# esp32_wroom_32_pwm.net
KiCad netlist of a schematic drawn in EAGLE
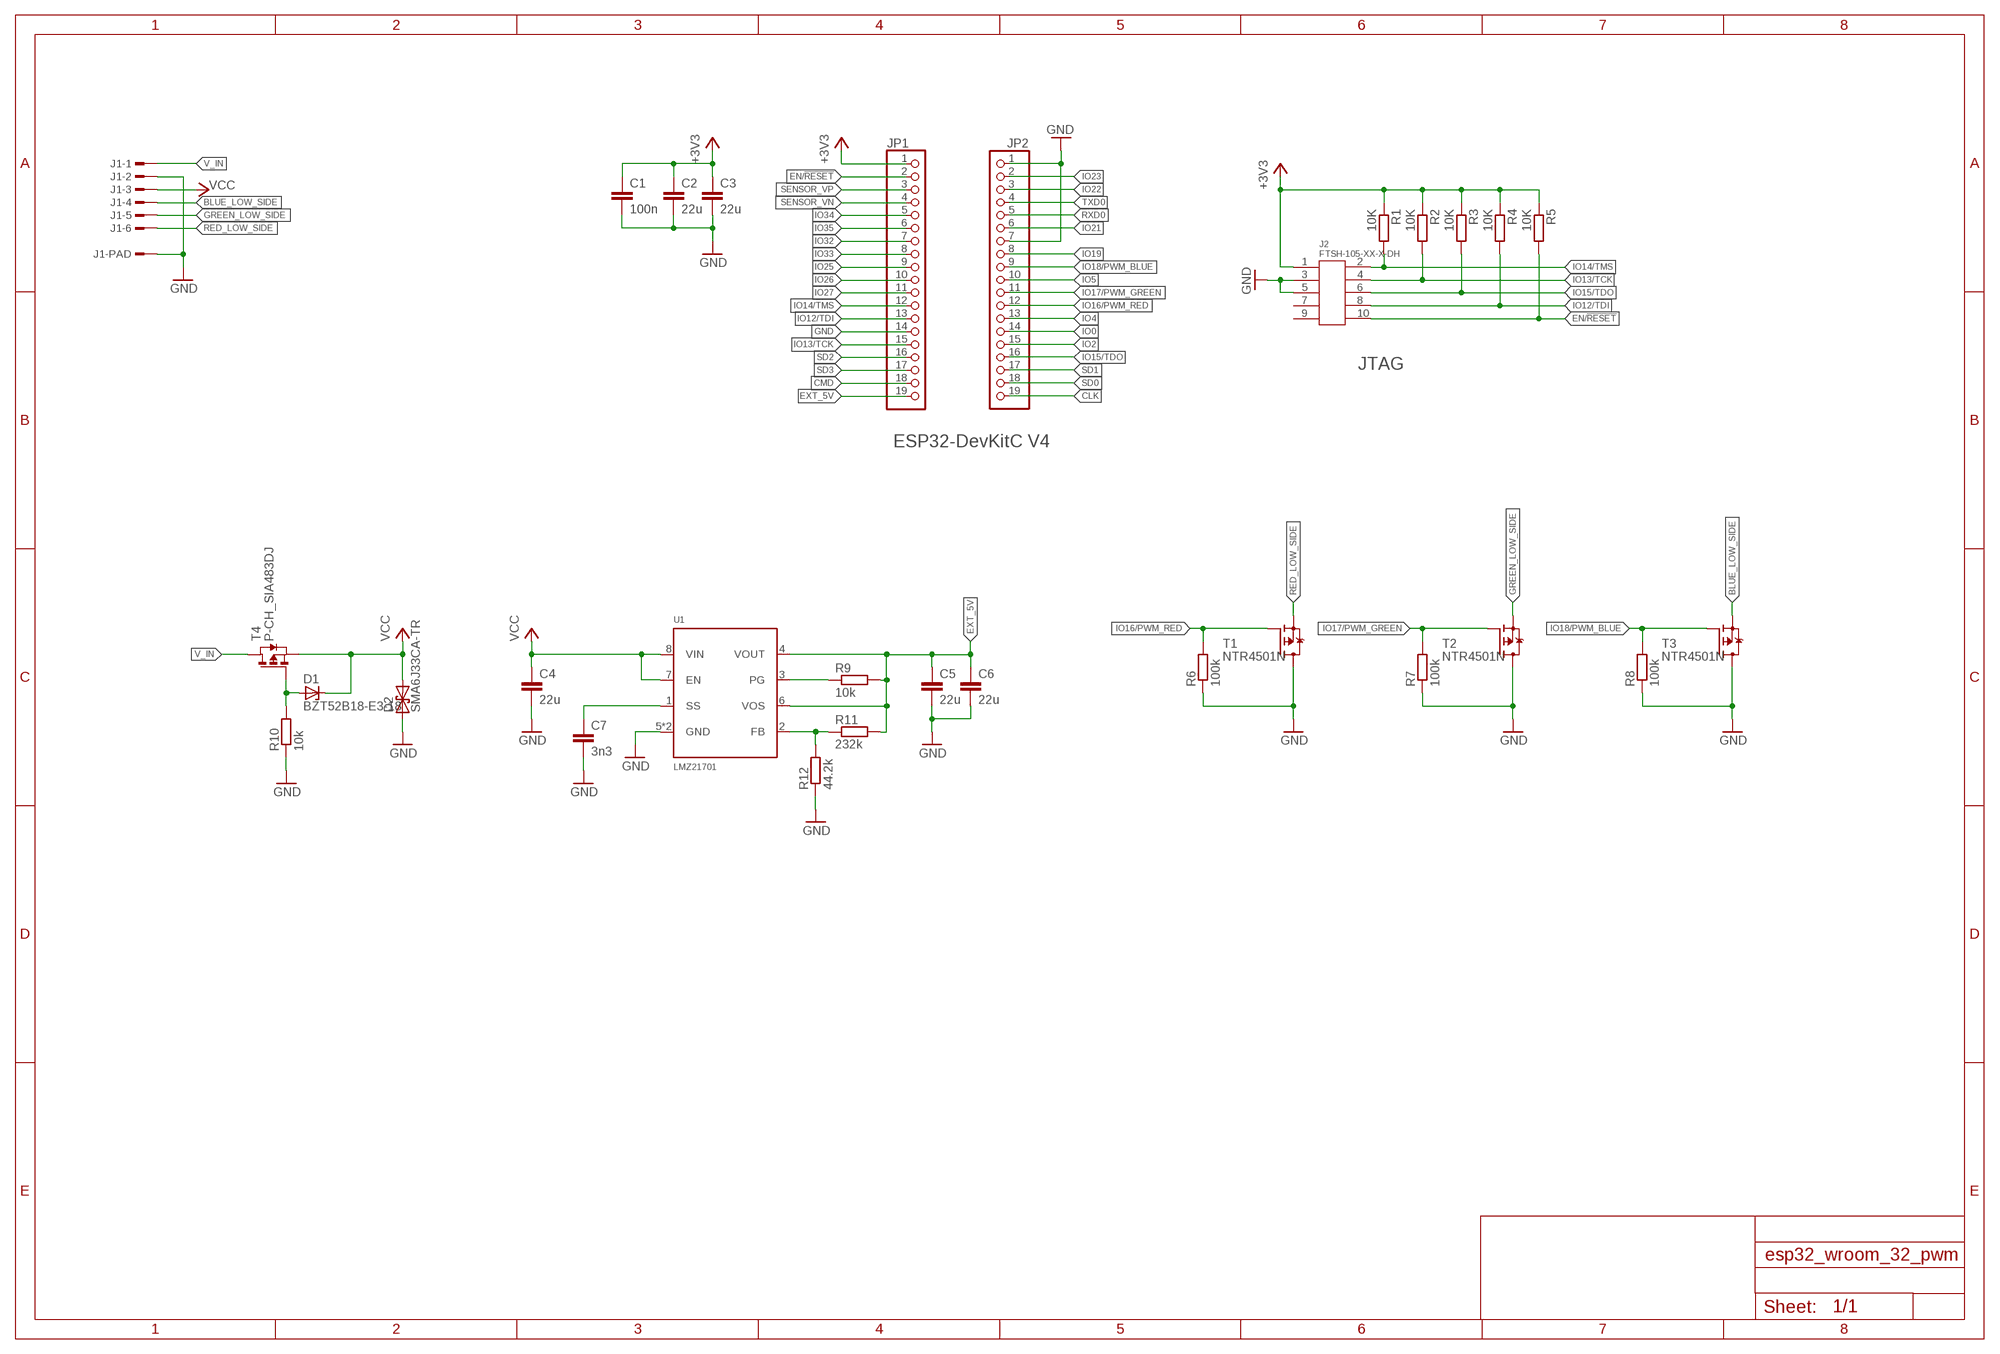
[diagram p0: schematic, sheet 1]

(export (version "E")
  (design (tool "Eeschema 10.0.6"))
  (components
    (comp (ref "C1")
      (value "100n")
      (footprint "eagle-import:C0603")
      (libsource (lib "eagle-import") (part "C-EUC0603"))
    )
    (comp (ref "C2")
      (value "22u")
      (footprint "eagle-import:C1210")
      (libsource (lib "eagle-import") (part "C-EUC1210"))
    )
    (comp (ref "C3")
      (value "22u")
      (footprint "eagle-import:C1210")
      (libsource (lib "eagle-import") (part "C-EUC1210"))
    )
    (comp (ref "C4")
      (value "22u")
      (footprint "eagle-import:C1210")
      (libsource (lib "eagle-import") (part "C-EUC1210"))
    )
    (comp (ref "C5")
      (value "22u")
      (footprint "eagle-import:C1210")
      (libsource (lib "eagle-import") (part "C-EUC1210"))
    )
    (comp (ref "C6")
      (value "22u")
      (footprint "eagle-import:C1210")
      (libsource (lib "eagle-import") (part "C-EUC1210"))
    )
    (comp (ref "C7")
      (value "3n3")
      (footprint "eagle-import:C0603")
      (libsource (lib "eagle-import") (part "C-EUC0603"))
    )
    (comp (ref "D1")
      (value "BZT52B18-E3-18")
      (footprint "eagle-import:SOD123F")
      (libsource (lib "eagle-import") (part "ZENER_BZT52B18-E3-18"))
    )
    (comp (ref "D2")
      (value "SMA6J33CA-TR")
      (footprint "eagle-import:DO214AC")
      (libsource (lib "eagle-import") (part "SMA6J33CA-TR"))
    )
    (comp (ref "J1")
      (value "292227-6")
      (footprint "eagle-import:292227-6")
      (libsource (lib "eagle-import") (part "292227-6"))
    )
    (comp (ref "J2")
      (value "FTSH-105-XX-X-DH")
      (footprint "eagle-import:FTSH-105-XX-XXX-DH")
      (libsource (lib "eagle-import") (part "FTSH-105-XX-X-DH"))
    )
    (comp (ref "JP1")
      (value "PINHD-1X19")
      (footprint "eagle-import:1X19")
      (libsource (lib "eagle-import") (part "PINHD-1X19"))
    )
    (comp (ref "JP2")
      (value "PINHD-1X19")
      (footprint "eagle-import:1X19")
      (libsource (lib "eagle-import") (part "PINHD-1X19"))
    )
    (comp (ref "R1")
      (value "10K")
      (footprint "eagle-import:R0603")
      (libsource (lib "eagle-import") (part "R-EU_R0603"))
    )
    (comp (ref "R2")
      (value "10K")
      (footprint "eagle-import:R0603")
      (libsource (lib "eagle-import") (part "R-EU_R0603"))
    )
    (comp (ref "R3")
      (value "10K")
      (footprint "eagle-import:R0603")
      (libsource (lib "eagle-import") (part "R-EU_R0603"))
    )
    (comp (ref "R4")
      (value "10K")
      (footprint "eagle-import:R0603")
      (libsource (lib "eagle-import") (part "R-EU_R0603"))
    )
    (comp (ref "R5")
      (value "10K")
      (footprint "eagle-import:R0603")
      (libsource (lib "eagle-import") (part "R-EU_R0603"))
    )
    (comp (ref "R6")
      (value "100k")
      (footprint "eagle-import:R0603")
      (libsource (lib "eagle-import") (part "R-EU_R0603"))
    )
    (comp (ref "R7")
      (value "100k")
      (footprint "eagle-import:R0603")
      (libsource (lib "eagle-import") (part "R-EU_R0603"))
    )
    (comp (ref "R8")
      (value "100k")
      (footprint "eagle-import:R0603")
      (libsource (lib "eagle-import") (part "R-EU_R0603"))
    )
    (comp (ref "R9")
      (value "10k")
      (footprint "eagle-import:R0603")
      (libsource (lib "eagle-import") (part "R-EU_R0603"))
    )
    (comp (ref "R10")
      (value "10k")
      (footprint "eagle-import:R0603")
      (libsource (lib "eagle-import") (part "R-EU_R0603"))
    )
    (comp (ref "R11")
      (value "232k")
      (footprint "eagle-import:R0603")
      (libsource (lib "eagle-import") (part "R-EU_R0603"))
    )
    (comp (ref "R12")
      (value "44.2k")
      (footprint "eagle-import:R0603")
      (libsource (lib "eagle-import") (part "R-EU_R0603"))
    )
    (comp (ref "T1")
      (value "NTR4501N")
      (footprint "eagle-import:SOT23")
      (libsource (lib "eagle-import") (part "NTR4501N"))
    )
    (comp (ref "T2")
      (value "NTR4501N")
      (footprint "eagle-import:SOT23")
      (libsource (lib "eagle-import") (part "NTR4501N"))
    )
    (comp (ref "T3")
      (value "NTR4501N")
      (footprint "eagle-import:SOT23")
      (libsource (lib "eagle-import") (part "NTR4501N"))
    )
    (comp (ref "T4")
      (value "P-CH_SIA483DJ")
      (footprint "eagle-import:POWERPAK_SC70-6L")
      (libsource (lib "eagle-import") (part "P-CH_SIA483DJ"))
    )
    (comp (ref "U1")
      (value "LMZ21701")
      (footprint "eagle-import:SIL0008E")
      (libsource (lib "eagle-import") (part "LMZ21701"))
    )
  )
  (nets
    (net (code "1") (name "+3V3") (class "Default")
      (node (ref "C1") (pin "1") (pinfunction "1_1") (pintype "passive"))
      (node (ref "C2") (pin "1") (pinfunction "1_1") (pintype "passive"))
      (node (ref "C3") (pin "1") (pinfunction "1_1") (pintype "passive"))
      (node (ref "J2") (pin "1") (pinfunction "1_1") (pintype "passive"))
      (node (ref "JP1") (pin "1") (pinfunction "1_1") (pintype "passive"))
      (node (ref "R1") (pin "1") (pinfunction "1_1") (pintype "passive"))
      (node (ref "R2") (pin "1") (pinfunction "1_1") (pintype "passive"))
      (node (ref "R3") (pin "1") (pinfunction "1_1") (pintype "passive"))
      (node (ref "R4") (pin "1") (pinfunction "1_1") (pintype "passive"))
      (node (ref "R5") (pin "1") (pinfunction "1_1") (pintype "passive"))
    )
    (net (code "2") (name "/EN{slash}~{RESET}") (class "Default")
      (node (ref "J2") (pin "10") (pinfunction "10_10") (pintype "passive"))
      (node (ref "JP1") (pin "2") (pinfunction "2_2") (pintype "passive"))
      (node (ref "R5") (pin "2") (pinfunction "2_2") (pintype "passive"))
    )
    (net (code "3") (name "BLUE_LOW_SIDE") (class "Default")
      (node (ref "J1") (pin "4") (pinfunction "1_4") (pintype "passive"))
      (node (ref "T3") (pin "2") (pinfunction "S_2") (pintype "passive"))
    )
    (net (code "4") (name "CLK") (class "Default")
      (node (ref "JP2") (pin "19") (pinfunction "19_19") (pintype "passive"))
    )
    (net (code "5") (name "CMD") (class "Default")
      (node (ref "JP1") (pin "18") (pinfunction "18_18") (pintype "passive"))
    )
    (net (code "6") (name "EXT_5V") (class "Default")
      (node (ref "C5") (pin "1") (pinfunction "1_1") (pintype "passive"))
      (node (ref "C6") (pin "1") (pinfunction "1_1") (pintype "passive"))
      (node (ref "JP1") (pin "19") (pinfunction "19_19") (pintype "passive"))
      (node (ref "R11") (pin "2") (pinfunction "2_2") (pintype "passive"))
      (node (ref "R9") (pin "2") (pinfunction "2_2") (pintype "passive"))
      (node (ref "U1") (pin "4") (pinfunction "VOUT_4") (pintype "passive"))
      (node (ref "U1") (pin "6") (pinfunction "VOS_6") (pintype "input"))
    )
    (net (code "7") (name "GND") (class "Default")
      (node (ref "C1") (pin "2") (pinfunction "2_2") (pintype "passive"))
      (node (ref "C2") (pin "2") (pinfunction "2_2") (pintype "passive"))
      (node (ref "C3") (pin "2") (pinfunction "2_2") (pintype "passive"))
      (node (ref "C4") (pin "2") (pinfunction "2_2") (pintype "passive"))
      (node (ref "C5") (pin "2") (pinfunction "2_2") (pintype "passive"))
      (node (ref "C6") (pin "2") (pinfunction "2_2") (pintype "passive"))
      (node (ref "C7") (pin "2") (pinfunction "2_2") (pintype "passive"))
      (node (ref "D2") (pin "A") (pinfunction "1_A") (pintype "passive"))
      (node (ref "J1") (pin "2") (pinfunction "1_2") (pintype "passive"))
      (node (ref "J1") (pin "PAD1") (pinfunction "1_PAD1") (pintype "passive"))
      (node (ref "J1") (pin "PAD2") (pinfunction "1_PAD2") (pintype "passive"))
      (node (ref "J2") (pin "3") (pinfunction "3_3") (pintype "passive"))
      (node (ref "J2") (pin "5") (pinfunction "5_5") (pintype "passive"))
      (node (ref "JP1") (pin "14") (pinfunction "14_14") (pintype "passive"))
      (node (ref "JP2") (pin "1") (pinfunction "1_1") (pintype "passive"))
      (node (ref "JP2") (pin "7") (pinfunction "7_7") (pintype "passive"))
      (node (ref "R10") (pin "1") (pinfunction "1_1") (pintype "passive"))
      (node (ref "R12") (pin "1") (pinfunction "1_1") (pintype "passive"))
      (node (ref "R6") (pin "1") (pinfunction "1_1") (pintype "passive"))
      (node (ref "R7") (pin "1") (pinfunction "1_1") (pintype "passive"))
      (node (ref "R8") (pin "1") (pinfunction "1_1") (pintype "passive"))
      (node (ref "T1") (pin "3") (pinfunction "D_3") (pintype "passive"))
      (node (ref "T2") (pin "3") (pinfunction "D_3") (pintype "passive"))
      (node (ref "T3") (pin "3") (pinfunction "D_3") (pintype "passive"))
      (node (ref "U1") (pin "5") (pinfunction "GND_5") (pintype "power_in"))
      (node (ref "U1") (pin "PAD") (pinfunction "GND_PAD") (pintype "power_in"))
    )
    (net (code "8") (name "GREEN_LOW_SIDE") (class "Default")
      (node (ref "J1") (pin "5") (pinfunction "1_5") (pintype "passive"))
      (node (ref "T2") (pin "2") (pinfunction "S_2") (pintype "passive"))
    )
    (net (code "9") (name "IO0") (class "Default")
      (node (ref "JP2") (pin "14") (pinfunction "14_14") (pintype "passive"))
    )
    (net (code "10") (name "IO2") (class "Default")
      (node (ref "JP2") (pin "15") (pinfunction "15_15") (pintype "passive"))
    )
    (net (code "11") (name "IO4") (class "Default")
      (node (ref "JP2") (pin "13") (pinfunction "13_13") (pintype "passive"))
    )
    (net (code "12") (name "IO5") (class "Default")
      (node (ref "JP2") (pin "10") (pinfunction "10_10") (pintype "passive"))
    )
    (net (code "13") (name "IO12{slash}TDI") (class "Default")
      (node (ref "J2") (pin "8") (pinfunction "8_8") (pintype "passive"))
      (node (ref "JP1") (pin "13") (pinfunction "13_13") (pintype "passive"))
      (node (ref "R4") (pin "2") (pinfunction "2_2") (pintype "passive"))
    )
    (net (code "14") (name "IO13{slash}TCK") (class "Default")
      (node (ref "J2") (pin "4") (pinfunction "4_4") (pintype "passive"))
      (node (ref "JP1") (pin "15") (pinfunction "15_15") (pintype "passive"))
      (node (ref "R2") (pin "2") (pinfunction "2_2") (pintype "passive"))
    )
    (net (code "15") (name "IO14{slash}TMS") (class "Default")
      (node (ref "J2") (pin "2") (pinfunction "2_2") (pintype "passive"))
      (node (ref "JP1") (pin "12") (pinfunction "12_12") (pintype "passive"))
      (node (ref "R1") (pin "2") (pinfunction "2_2") (pintype "passive"))
    )
    (net (code "16") (name "IO15{slash}TDO") (class "Default")
      (node (ref "J2") (pin "6") (pinfunction "6_6") (pintype "passive"))
      (node (ref "JP2") (pin "16") (pinfunction "16_16") (pintype "passive"))
      (node (ref "R3") (pin "2") (pinfunction "2_2") (pintype "passive"))
    )
    (net (code "17") (name "IO16{slash}PWM_RED") (class "Default")
      (node (ref "JP2") (pin "12") (pinfunction "12_12") (pintype "passive"))
      (node (ref "R6") (pin "2") (pinfunction "2_2") (pintype "passive"))
      (node (ref "T1") (pin "1") (pinfunction "G_1") (pintype "passive"))
    )
    (net (code "18") (name "IO17{slash}PWM_GREEN") (class "Default")
      (node (ref "JP2") (pin "11") (pinfunction "11_11") (pintype "passive"))
      (node (ref "R7") (pin "2") (pinfunction "2_2") (pintype "passive"))
      (node (ref "T2") (pin "1") (pinfunction "G_1") (pintype "passive"))
    )
    (net (code "19") (name "IO18{slash}PWM_BLUE") (class "Default")
      (node (ref "JP2") (pin "9") (pinfunction "9_9") (pintype "passive"))
      (node (ref "R8") (pin "2") (pinfunction "2_2") (pintype "passive"))
      (node (ref "T3") (pin "1") (pinfunction "G_1") (pintype "passive"))
    )
    (net (code "20") (name "IO19") (class "Default")
      (node (ref "JP2") (pin "8") (pinfunction "8_8") (pintype "passive"))
    )
    (net (code "21") (name "IO21") (class "Default")
      (node (ref "JP2") (pin "6") (pinfunction "6_6") (pintype "passive"))
    )
    (net (code "22") (name "IO22") (class "Default")
      (node (ref "JP2") (pin "3") (pinfunction "3_3") (pintype "passive"))
    )
    (net (code "23") (name "IO23") (class "Default")
      (node (ref "JP2") (pin "2") (pinfunction "2_2") (pintype "passive"))
    )
    (net (code "24") (name "IO25") (class "Default")
      (node (ref "JP1") (pin "9") (pinfunction "9_9") (pintype "passive"))
    )
    (net (code "25") (name "IO26") (class "Default")
      (node (ref "JP1") (pin "10") (pinfunction "10_10") (pintype "passive"))
    )
    (net (code "26") (name "IO27") (class "Default")
      (node (ref "JP1") (pin "11") (pinfunction "11_11") (pintype "passive"))
    )
    (net (code "27") (name "IO32") (class "Default")
      (node (ref "JP1") (pin "7") (pinfunction "7_7") (pintype "passive"))
    )
    (net (code "28") (name "IO33") (class "Default")
      (node (ref "JP1") (pin "8") (pinfunction "8_8") (pintype "passive"))
    )
    (net (code "29") (name "IO34") (class "Default")
      (node (ref "JP1") (pin "5") (pinfunction "5_5") (pintype "passive"))
    )
    (net (code "30") (name "IO35") (class "Default")
      (node (ref "JP1") (pin "6") (pinfunction "6_6") (pintype "passive"))
    )
    (net (code "31") (name "Net-(T4-G)") (class "Default")
      (node (ref "D1") (pin "A") (pinfunction "A_A") (pintype "passive"))
      (node (ref "R10") (pin "2") (pinfunction "2_2") (pintype "passive"))
      (node (ref "T4") (pin "3") (pinfunction "G_3") (pintype "passive"))
    )
    (net (code "32") (name "Net-(U1-FB)") (class "Default")
      (node (ref "R11") (pin "1") (pinfunction "1_1") (pintype "passive"))
      (node (ref "R12") (pin "2") (pinfunction "2_2") (pintype "passive"))
      (node (ref "U1") (pin "2") (pinfunction "FB_2") (pintype "input"))
    )
    (net (code "33") (name "Net-(U1-PG)") (class "Default")
      (node (ref "R9") (pin "1") (pinfunction "1_1") (pintype "passive"))
      (node (ref "U1") (pin "3") (pinfunction "PG_3") (pintype "output"))
    )
    (net (code "34") (name "Net-(U1-SS)") (class "Default")
      (node (ref "C7") (pin "1") (pinfunction "1_1") (pintype "passive"))
      (node (ref "U1") (pin "1") (pinfunction "SS_1") (pintype "passive"))
    )
    (net (code "35") (name "RED_LOW_SIDE") (class "Default")
      (node (ref "J1") (pin "6") (pinfunction "1_6") (pintype "passive"))
      (node (ref "T1") (pin "2") (pinfunction "S_2") (pintype "passive"))
    )
    (net (code "36") (name "RXD0") (class "Default")
      (node (ref "JP2") (pin "5") (pinfunction "5_5") (pintype "passive"))
    )
    (net (code "37") (name "SD0") (class "Default")
      (node (ref "JP2") (pin "18") (pinfunction "18_18") (pintype "passive"))
    )
    (net (code "38") (name "SD1") (class "Default")
      (node (ref "JP2") (pin "17") (pinfunction "17_17") (pintype "passive"))
    )
    (net (code "39") (name "SD2") (class "Default")
      (node (ref "JP1") (pin "16") (pinfunction "16_16") (pintype "passive"))
    )
    (net (code "40") (name "SD3") (class "Default")
      (node (ref "JP1") (pin "17") (pinfunction "17_17") (pintype "passive"))
    )
    (net (code "41") (name "SENSOR_VN") (class "Default")
      (node (ref "JP1") (pin "4") (pinfunction "4_4") (pintype "passive"))
    )
    (net (code "42") (name "SENSOR_VP") (class "Default")
      (node (ref "JP1") (pin "3") (pinfunction "3_3") (pintype "passive"))
    )
    (net (code "43") (name "TXD0") (class "Default")
      (node (ref "JP2") (pin "4") (pinfunction "4_4") (pintype "passive"))
    )
    (net (code "44") (name "VCC") (class "Default")
      (node (ref "C4") (pin "1") (pinfunction "1_1") (pintype "passive"))
      (node (ref "D1") (pin "C") (pinfunction "C_C") (pintype "passive"))
      (node (ref "D2") (pin "C") (pinfunction "2_C") (pintype "passive"))
      (node (ref "J1") (pin "3") (pinfunction "1_3") (pintype "passive"))
      (node (ref "T4") (pin "4") (pinfunction "S_4") (pintype "passive"))
      (node (ref "T4") (pin "TH_S") (pinfunction "S_TH_S") (pintype "passive"))
      (node (ref "U1") (pin "7") (pinfunction "EN_7") (pintype "input"))
      (node (ref "U1") (pin "8") (pinfunction "VIN_8") (pintype "power_in"))
    )
    (net (code "45") (name "V_IN") (class "Default")
      (node (ref "J1") (pin "1") (pinfunction "1_1") (pintype "passive"))
      (node (ref "T4") (pin "1") (pinfunction "D_1") (pintype "passive"))
      (node (ref "T4") (pin "2") (pinfunction "D_2") (pintype "passive"))
      (node (ref "T4") (pin "5") (pinfunction "D_5") (pintype "passive"))
      (node (ref "T4") (pin "6") (pinfunction "D_6") (pintype "passive"))
      (node (ref "T4") (pin "TH_D") (pinfunction "D_TH_D") (pintype "passive"))
    )
    (net (code "46") (name "unconnected-(J2-Pad7)") (class "Default")
      (node (ref "J2") (pin "7") (pinfunction "7_7") (pintype "passive"))
    )
    (net (code "47") (name "unconnected-(J2-Pad9)") (class "Default")
      (node (ref "J2") (pin "9") (pinfunction "9_9") (pintype "passive"))
    )
  )
)
